# Sensors.net
KiCad netlist of a schematic drawn in Altium Designer
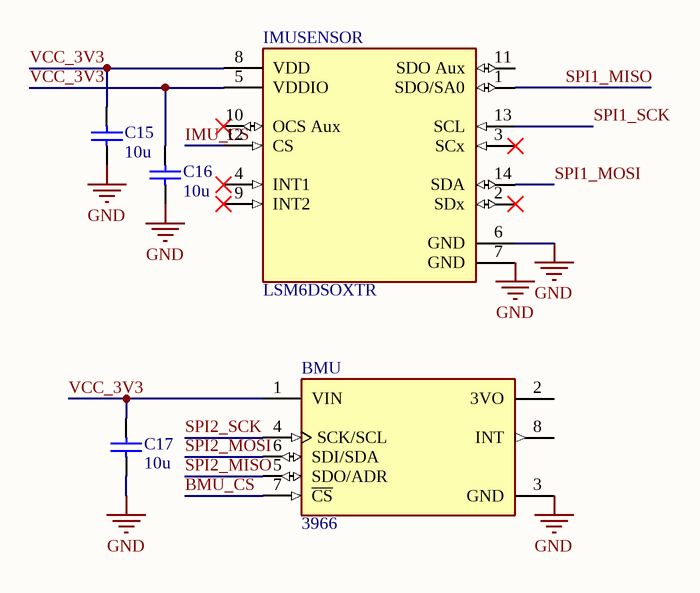
[diagram p0: Sensors.SchDoc]

(export (version "E")
  (design (tool "Eeschema 10.0.6"))
  (components
    (comp (ref "BMU")
      (value "3966")
      (footprint "FP-3966-MFG")
      (description "BMP388 - PRECISION BAROMETRIC PR")
      (libsource (lib "Altium Content Vault") (part "7ec954515874f1695838194320a9f7f"))
    )
    (comp (ref "C15")
      (value "10u")
      (description "Capacitor")
      (libsource (lib "Simulation Generic Components") (part "Capacitor"))
    )
    (comp (ref "C16")
      (value "10u")
      (description "Capacitor")
      (libsource (lib "Simulation Generic Components") (part "Capacitor"))
    )
    (comp (ref "C17")
      (value "10u")
      (description "Capacitor")
      (libsource (lib "Simulation Generic Components") (part "Capacitor"))
    )
    (comp (ref "IMUSENSOR")
      (value "LSM6DSOXTR")
      (footprint "FP-LGA-14L-DM00249496-MFG")
      (description "INEMO INERTIAL MODULE: 3D ACCELE")
      (fields
        (field (name "OCTOPART") "https://octopart.com/lsm6dsoxtr-stmicroelectronics-98102600")
        (field (name "MANUFACTURER") "STMicroelectronics")
      )
      (libsource (lib "Altium Content Vault") (part "e907d670a73553dd54601dfd5d274f3"))
    )
  )
  (nets
    (net (code "1") (name "/BMU_CS") (class "Default")
      (node (ref "BMU") (pin "7") (pinfunction "~{CS}_7") (pintype "input"))
    )
    (net (code "2") (name "/IMU_CS") (class "Default")
      (node (ref "IMUSENSOR") (pin "12") (pinfunction "CS_12") (pintype "input"))
    )
    (net (code "3") (name "/SPI1_MISO") (class "Default")
      (node (ref "IMUSENSOR") (pin "1") (pinfunction "SDO/SA0_1") (pintype "bidirectional"))
    )
    (net (code "4") (name "/SPI1_MOSI") (class "Default")
      (node (ref "IMUSENSOR") (pin "14") (pinfunction "SDA_14") (pintype "bidirectional"))
    )
    (net (code "5") (name "/SPI1_SCK") (class "Default")
      (node (ref "IMUSENSOR") (pin "13") (pinfunction "SCL_13") (pintype "input"))
    )
    (net (code "6") (name "/SPI2_MISO") (class "Default")
      (node (ref "BMU") (pin "5") (pinfunction "SDO/ADR_5") (pintype "bidirectional"))
    )
    (net (code "7") (name "/SPI2_MOSI") (class "Default")
      (node (ref "BMU") (pin "6") (pinfunction "SDI/SDA_6") (pintype "bidirectional"))
    )
    (net (code "8") (name "/SPI2_SCK") (class "Default")
      (node (ref "BMU") (pin "4") (pinfunction "SCK/SCL_4") (pintype "input"))
    )
    (net (code "9") (name "/VCC_3V3") (class "Default")
      (node (ref "BMU") (pin "1") (pinfunction "VIN_1") (pintype "power_in"))
      (node (ref "C15") (pin "2") (pinfunction "2_2") (pintype "passive"))
      (node (ref "C16") (pin "2") (pinfunction "2_2") (pintype "passive"))
      (node (ref "C17") (pin "2") (pinfunction "2_2") (pintype "passive"))
      (node (ref "IMUSENSOR") (pin "5") (pinfunction "VDDIO_5") (pintype "power_in"))
      (node (ref "IMUSENSOR") (pin "8") (pinfunction "VDD_8") (pintype "power_in"))
    )
    (net (code "10") (name "GND") (class "Default")
      (node (ref "BMU") (pin "3") (pinfunction "GND_3") (pintype "power_in"))
      (node (ref "C15") (pin "1") (pinfunction "1_1") (pintype "passive"))
      (node (ref "C16") (pin "1") (pinfunction "1_1") (pintype "passive"))
      (node (ref "C17") (pin "1") (pinfunction "1_1") (pintype "passive"))
      (node (ref "IMUSENSOR") (pin "6") (pinfunction "GND_6") (pintype "power_in"))
      (node (ref "IMUSENSOR") (pin "7") (pinfunction "GND_7") (pintype "power_in"))
    )
    (net (code "11") (name "unconnected-(BMU-3VO-Pad2)") (class "Default")
      (node (ref "BMU") (pin "2") (pinfunction "3VO_2") (pintype "power_in"))
    )
    (net (code "12") (name "unconnected-(BMU-INT-Pad8)") (class "Default")
      (node (ref "BMU") (pin "8") (pinfunction "INT_8") (pintype "output"))
    )
    (net (code "13") (name "unconnected-(IMUSENSOR-INT1-Pad4)") (class "Default")
      (node (ref "IMUSENSOR") (pin "4") (pinfunction "INT1_4") (pintype "input+no_connect"))
    )
    (net (code "14") (name "unconnected-(IMUSENSOR-INT2-Pad9)") (class "Default")
      (node (ref "IMUSENSOR") (pin "9") (pinfunction "INT2_9") (pintype "input+no_connect"))
    )
    (net (code "15") (name "unconnected-(IMUSENSOR-OCS_Aux-Pad10)") (class "Default")
      (node (ref "IMUSENSOR") (pin "10") (pinfunction "OCS_Aux_10") (pintype "bidirectional+no_connect"))
    )
    (net (code "16") (name "unconnected-(IMUSENSOR-SCx-Pad3)") (class "Default")
      (node (ref "IMUSENSOR") (pin "3") (pinfunction "SCx_3") (pintype "input+no_connect"))
    )
    (net (code "17") (name "unconnected-(IMUSENSOR-SDO_Aux-Pad11)") (class "Default")
      (node (ref "IMUSENSOR") (pin "11") (pinfunction "SDO_Aux_11") (pintype "bidirectional"))
    )
    (net (code "18") (name "unconnected-(IMUSENSOR-SDx-Pad2)") (class "Default")
      (node (ref "IMUSENSOR") (pin "2") (pinfunction "SDx_2") (pintype "bidirectional+no_connect"))
    )
  )
)
